# atmega_simon_says.net
KiCad netlist of a schematic drawn in EAGLE
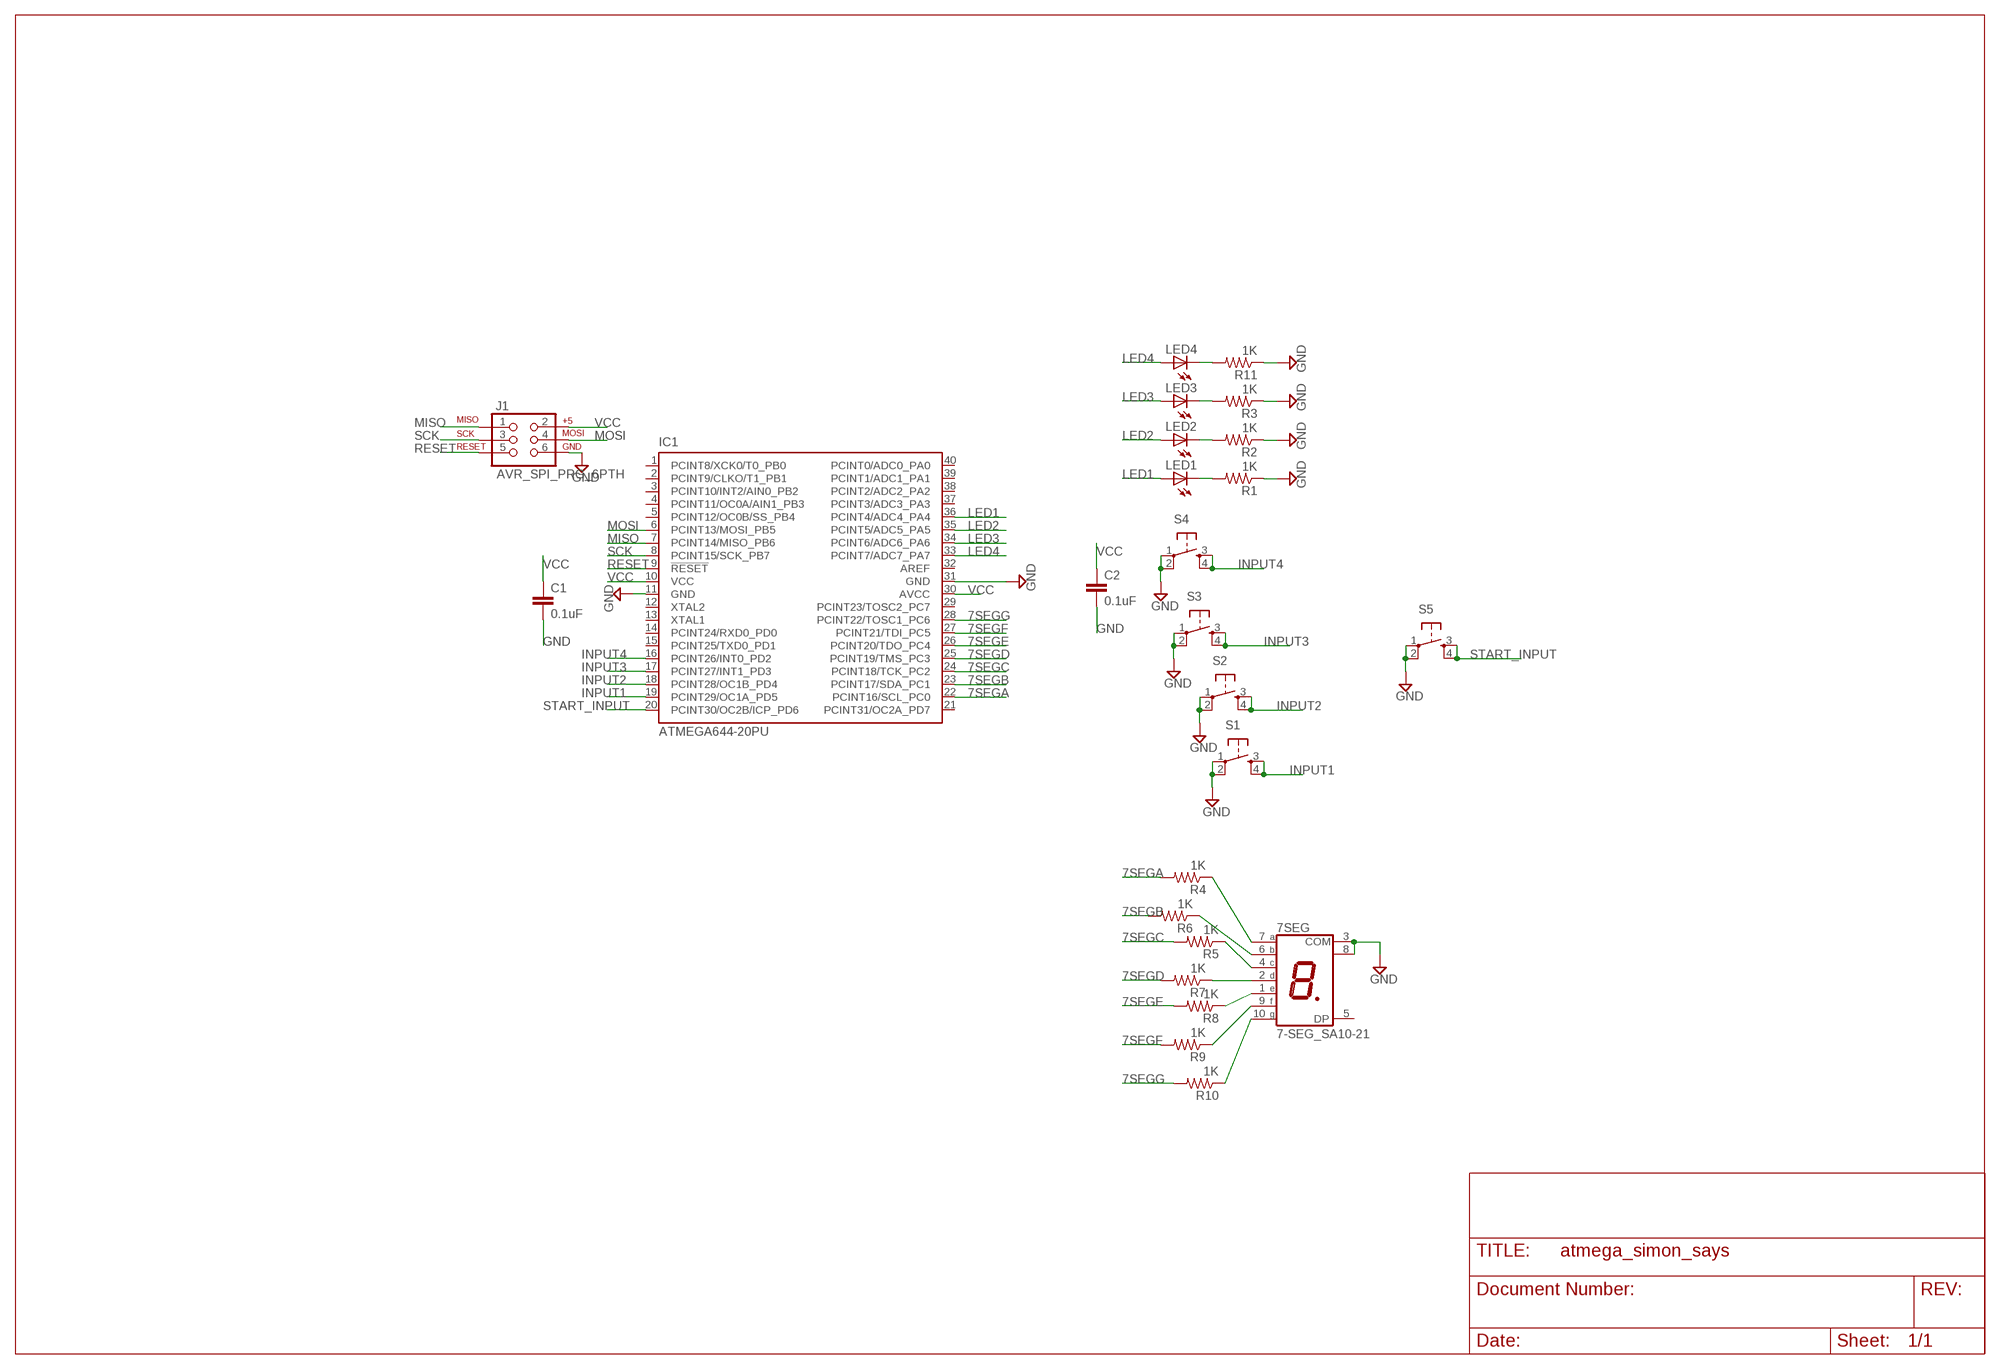
[diagram p0: schematic, sheet 1]

(export (version "E")
  (design (tool "Eeschema 10.0.6"))
  (components
    (comp (ref "7SEG")
      (value "7-SEG_SA10-21")
      (footprint "eagle-import:SA10-21")
      (libsource (lib "eagle-import") (part "7-SEG_SA10-21"))
    )
    (comp (ref "C1")
      (value "0.1uF")
      (footprint "eagle-import:0603-CAP")
      (libsource (lib "eagle-import") (part "0.1UF-25V(+80/-20%)(0603)"))
    )
    (comp (ref "C2")
      (value "0.1uF")
      (footprint "eagle-import:0603-CAP")
      (libsource (lib "eagle-import") (part "0.1UF-25V(+80/-20%)(0603)"))
    )
    (comp (ref "IC1")
      (value "ATMEGA644-20PU")
      (footprint "eagle-import:DIL40")
      (libsource (lib "eagle-import") (part "ATMEGA644-PU20"))
    )
    (comp (ref "J1")
      (value "AVR_SPI_PRG_6PTH")
      (footprint "eagle-import:2X3")
      (libsource (lib "eagle-import") (part "AVR_SPI_PRG_6PTH"))
    )
    (comp (ref "LED1")
      (value "LED3MM")
      (footprint "eagle-import:LED3MM")
      (libsource (lib "eagle-import") (part "LED3MM"))
    )
    (comp (ref "LED2")
      (value "LED3MM")
      (footprint "eagle-import:LED3MM")
      (libsource (lib "eagle-import") (part "LED3MM"))
    )
    (comp (ref "LED3")
      (value "LED3MM")
      (footprint "eagle-import:LED3MM")
      (libsource (lib "eagle-import") (part "LED3MM"))
    )
    (comp (ref "LED4")
      (value "LED3MM")
      (footprint "eagle-import:LED3MM")
      (libsource (lib "eagle-import") (part "LED3MM"))
    )
    (comp (ref "R1")
      (value "1K")
      (footprint "eagle-import:0204_5")
      (libsource (lib "eagle-import") (part "R-US_0204/5"))
    )
    (comp (ref "R2")
      (value "1K")
      (footprint "eagle-import:0204_5")
      (libsource (lib "eagle-import") (part "R-US_0204/5"))
    )
    (comp (ref "R3")
      (value "1K")
      (footprint "eagle-import:0204_5")
      (libsource (lib "eagle-import") (part "R-US_0204/5"))
    )
    (comp (ref "R4")
      (value "1K")
      (footprint "eagle-import:0204_5")
      (libsource (lib "eagle-import") (part "R-US_0204/5"))
    )
    (comp (ref "R5")
      (value "1K")
      (footprint "eagle-import:0204_5")
      (libsource (lib "eagle-import") (part "R-US_0204/5"))
    )
    (comp (ref "R6")
      (value "1K")
      (footprint "eagle-import:0204_5")
      (libsource (lib "eagle-import") (part "R-US_0204/5"))
    )
    (comp (ref "R7")
      (value "1K")
      (footprint "eagle-import:0204_5")
      (libsource (lib "eagle-import") (part "R-US_0204/5"))
    )
    (comp (ref "R8")
      (value "1K")
      (footprint "eagle-import:0204_5")
      (libsource (lib "eagle-import") (part "R-US_0204/5"))
    )
    (comp (ref "R9")
      (value "1K")
      (footprint "eagle-import:0204_5")
      (libsource (lib "eagle-import") (part "R-US_0204/5"))
    )
    (comp (ref "R10")
      (value "1K")
      (footprint "eagle-import:0204_5")
      (libsource (lib "eagle-import") (part "R-US_0204/5"))
    )
    (comp (ref "R11")
      (value "1K")
      (footprint "eagle-import:0204_5")
      (libsource (lib "eagle-import") (part "R-US_0204/5"))
    )
    (comp (ref "S1")
      (value "TAC_SWITCHPTH")
      (footprint "eagle-import:TACTILE-PTH")
      (libsource (lib "eagle-import") (part "TAC_SWITCHPTH"))
    )
    (comp (ref "S2")
      (value "TAC_SWITCHPTH")
      (footprint "eagle-import:TACTILE-PTH")
      (libsource (lib "eagle-import") (part "TAC_SWITCHPTH"))
    )
    (comp (ref "S3")
      (value "TAC_SWITCHPTH")
      (footprint "eagle-import:TACTILE-PTH")
      (libsource (lib "eagle-import") (part "TAC_SWITCHPTH"))
    )
    (comp (ref "S4")
      (value "TAC_SWITCHPTH")
      (footprint "eagle-import:TACTILE-PTH")
      (libsource (lib "eagle-import") (part "TAC_SWITCHPTH"))
    )
    (comp (ref "S5")
      (value "TAC_SWITCHPTH")
      (footprint "eagle-import:TACTILE-PTH")
      (libsource (lib "eagle-import") (part "TAC_SWITCHPTH"))
    )
  )
  (nets
    (net (code "1") (name "/7SEGA") (class "Default")
      (node (ref "IC1") (pin "22") (pinfunction "PCINT16/SCL_PC0_22") (pintype "bidirectional"))
      (node (ref "R4") (pin "2") (pinfunction "2_2") (pintype "passive"))
    )
    (net (code "2") (name "/7SEGB") (class "Default")
      (node (ref "IC1") (pin "23") (pinfunction "PCINT17/SDA_PC1_23") (pintype "bidirectional"))
      (node (ref "R6") (pin "2") (pinfunction "2_2") (pintype "passive"))
    )
    (net (code "3") (name "/7SEGC") (class "Default")
      (node (ref "IC1") (pin "24") (pinfunction "PCINT18/TCK_PC2_24") (pintype "bidirectional"))
      (node (ref "R5") (pin "2") (pinfunction "2_2") (pintype "passive"))
    )
    (net (code "4") (name "/7SEGD") (class "Default")
      (node (ref "IC1") (pin "25") (pinfunction "PCINT19/TMS_PC3_25") (pintype "bidirectional"))
      (node (ref "R7") (pin "2") (pinfunction "2_2") (pintype "passive"))
    )
    (net (code "5") (name "/7SEGE") (class "Default")
      (node (ref "IC1") (pin "26") (pinfunction "PCINT20/TDO_PC4_26") (pintype "bidirectional"))
      (node (ref "R8") (pin "2") (pinfunction "2_2") (pintype "passive"))
    )
    (net (code "6") (name "/7SEGF") (class "Default")
      (node (ref "IC1") (pin "27") (pinfunction "PCINT21/TDI_PC5_27") (pintype "bidirectional"))
      (node (ref "R9") (pin "2") (pinfunction "2_2") (pintype "passive"))
    )
    (net (code "7") (name "/7SEGG") (class "Default")
      (node (ref "IC1") (pin "28") (pinfunction "PCINT22/TOSC1_PC6_28") (pintype "bidirectional"))
      (node (ref "R10") (pin "2") (pinfunction "2_2") (pintype "passive"))
    )
    (net (code "8") (name "/INPUT1") (class "Default")
      (node (ref "IC1") (pin "19") (pinfunction "PCINT29/OC1A_PD5_19") (pintype "bidirectional"))
      (node (ref "S1") (pin "3") (pinfunction "3_3") (pintype "passive"))
      (node (ref "S1") (pin "4") (pinfunction "4_4") (pintype "passive"))
    )
    (net (code "9") (name "/INPUT2") (class "Default")
      (node (ref "IC1") (pin "18") (pinfunction "PCINT28/OC1B_PD4_18") (pintype "bidirectional"))
      (node (ref "S2") (pin "3") (pinfunction "3_3") (pintype "passive"))
      (node (ref "S2") (pin "4") (pinfunction "4_4") (pintype "passive"))
    )
    (net (code "10") (name "/INPUT3") (class "Default")
      (node (ref "IC1") (pin "17") (pinfunction "PCINT27/INT1_PD3_17") (pintype "bidirectional"))
      (node (ref "S3") (pin "3") (pinfunction "3_3") (pintype "passive"))
      (node (ref "S3") (pin "4") (pinfunction "4_4") (pintype "passive"))
    )
    (net (code "11") (name "/INPUT4") (class "Default")
      (node (ref "IC1") (pin "16") (pinfunction "PCINT26/INT0_PD2_16") (pintype "bidirectional"))
      (node (ref "S4") (pin "3") (pinfunction "3_3") (pintype "passive"))
      (node (ref "S4") (pin "4") (pinfunction "4_4") (pintype "passive"))
    )
    (net (code "12") (name "/LED1") (class "Default")
      (node (ref "IC1") (pin "36") (pinfunction "PCINT4/ADC4_PA4_36") (pintype "bidirectional"))
      (node (ref "LED1") (pin "A") (pinfunction "A_A") (pintype "passive"))
    )
    (net (code "13") (name "/LED2") (class "Default")
      (node (ref "IC1") (pin "35") (pinfunction "PCINT5/ADC5_PA5_35") (pintype "bidirectional"))
      (node (ref "LED2") (pin "A") (pinfunction "A_A") (pintype "passive"))
    )
    (net (code "14") (name "/LED3") (class "Default")
      (node (ref "IC1") (pin "34") (pinfunction "PCINT6/ADC6_PA6_34") (pintype "bidirectional"))
      (node (ref "LED3") (pin "A") (pinfunction "A_A") (pintype "passive"))
    )
    (net (code "15") (name "/LED4") (class "Default")
      (node (ref "IC1") (pin "33") (pinfunction "PCINT7/ADC7_PA7_33") (pintype "bidirectional"))
      (node (ref "LED4") (pin "A") (pinfunction "A_A") (pintype "passive"))
    )
    (net (code "16") (name "/MISO") (class "Default")
      (node (ref "IC1") (pin "7") (pinfunction "PCINT14/MISO_PB6_7") (pintype "bidirectional"))
      (node (ref "J1") (pin "1") (pinfunction "1_1") (pintype "passive"))
    )
    (net (code "17") (name "/MOSI") (class "Default")
      (node (ref "IC1") (pin "6") (pinfunction "PCINT13/MOSI_PB5_6") (pintype "bidirectional"))
      (node (ref "J1") (pin "4") (pinfunction "4_4") (pintype "passive"))
    )
    (net (code "18") (name "/RESET") (class "Default")
      (node (ref "IC1") (pin "9") (pinfunction "~{RESET}_9") (pintype "input"))
      (node (ref "J1") (pin "5") (pinfunction "5_5") (pintype "passive"))
    )
    (net (code "19") (name "/SCK") (class "Default")
      (node (ref "IC1") (pin "8") (pinfunction "PCINT15/SCK_PB7_8") (pintype "bidirectional"))
      (node (ref "J1") (pin "3") (pinfunction "3_3") (pintype "passive"))
    )
    (net (code "20") (name "/START_INPUT") (class "Default")
      (node (ref "IC1") (pin "20") (pinfunction "PCINT30/OC2B/ICP_PD6_20") (pintype "bidirectional"))
      (node (ref "S5") (pin "3") (pinfunction "3_3") (pintype "passive"))
      (node (ref "S5") (pin "4") (pinfunction "4_4") (pintype "passive"))
    )
    (net (code "21") (name "/VCC") (class "Default")
      (node (ref "C1") (pin "1") (pinfunction "1_1") (pintype "passive"))
      (node (ref "C2") (pin "1") (pinfunction "1_1") (pintype "passive"))
      (node (ref "IC1") (pin "10") (pinfunction "VCC_10") (pintype "power_in"))
      (node (ref "IC1") (pin "30") (pinfunction "AVCC_30") (pintype "power_in"))
      (node (ref "J1") (pin "2") (pinfunction "2_2") (pintype "passive"))
    )
    (net (code "22") (name "GND") (class "Default")
      (node (ref "7SEG") (pin "3") (pinfunction "COM_3") (pintype "passive"))
      (node (ref "7SEG") (pin "8") (pinfunction "COM_8") (pintype "passive"))
      (node (ref "C1") (pin "2") (pinfunction "2_2") (pintype "passive"))
      (node (ref "C2") (pin "2") (pinfunction "2_2") (pintype "passive"))
      (node (ref "IC1") (pin "11") (pinfunction "GND_11") (pintype "power_in"))
      (node (ref "IC1") (pin "31") (pinfunction "GND_31") (pintype "power_in"))
      (node (ref "J1") (pin "6") (pinfunction "6_6") (pintype "passive"))
      (node (ref "R1") (pin "1") (pinfunction "1_1") (pintype "passive"))
      (node (ref "R11") (pin "1") (pinfunction "1_1") (pintype "passive"))
      (node (ref "R2") (pin "1") (pinfunction "1_1") (pintype "passive"))
      (node (ref "R3") (pin "1") (pinfunction "1_1") (pintype "passive"))
      (node (ref "S1") (pin "1") (pinfunction "1_1") (pintype "passive"))
      (node (ref "S1") (pin "2") (pinfunction "2_2") (pintype "passive"))
      (node (ref "S2") (pin "1") (pinfunction "1_1") (pintype "passive"))
      (node (ref "S2") (pin "2") (pinfunction "2_2") (pintype "passive"))
      (node (ref "S3") (pin "1") (pinfunction "1_1") (pintype "passive"))
      (node (ref "S3") (pin "2") (pinfunction "2_2") (pintype "passive"))
      (node (ref "S4") (pin "1") (pinfunction "1_1") (pintype "passive"))
      (node (ref "S4") (pin "2") (pinfunction "2_2") (pintype "passive"))
      (node (ref "S5") (pin "1") (pinfunction "1_1") (pintype "passive"))
      (node (ref "S5") (pin "2") (pinfunction "2_2") (pintype "passive"))
    )
    (net (code "23") (name "Net-(7SEG-A)") (class "Default")
      (node (ref "7SEG") (pin "7") (pinfunction "A_7") (pintype "passive"))
      (node (ref "R4") (pin "1") (pinfunction "1_1") (pintype "passive"))
    )
    (net (code "24") (name "Net-(7SEG-B)") (class "Default")
      (node (ref "7SEG") (pin "6") (pinfunction "B_6") (pintype "passive"))
      (node (ref "R6") (pin "1") (pinfunction "1_1") (pintype "passive"))
    )
    (net (code "25") (name "Net-(7SEG-C)") (class "Default")
      (node (ref "7SEG") (pin "4") (pinfunction "C_4") (pintype "passive"))
      (node (ref "R5") (pin "1") (pinfunction "1_1") (pintype "passive"))
    )
    (net (code "26") (name "Net-(7SEG-D)") (class "Default")
      (node (ref "7SEG") (pin "2") (pinfunction "D_2") (pintype "passive"))
      (node (ref "R7") (pin "1") (pinfunction "1_1") (pintype "passive"))
    )
    (net (code "27") (name "Net-(7SEG-E)") (class "Default")
      (node (ref "7SEG") (pin "1") (pinfunction "E_1") (pintype "passive"))
      (node (ref "R8") (pin "1") (pinfunction "1_1") (pintype "passive"))
    )
    (net (code "28") (name "Net-(7SEG-F)") (class "Default")
      (node (ref "7SEG") (pin "9") (pinfunction "F_9") (pintype "passive"))
      (node (ref "R9") (pin "1") (pinfunction "1_1") (pintype "passive"))
    )
    (net (code "29") (name "Net-(7SEG-G)") (class "Default")
      (node (ref "7SEG") (pin "10") (pinfunction "G_10") (pintype "passive"))
      (node (ref "R10") (pin "1") (pinfunction "1_1") (pintype "passive"))
    )
    (net (code "30") (name "Net-(LED1-C)") (class "Default")
      (node (ref "LED1") (pin "K") (pinfunction "C_K") (pintype "passive"))
      (node (ref "R1") (pin "2") (pinfunction "2_2") (pintype "passive"))
    )
    (net (code "31") (name "Net-(LED2-C)") (class "Default")
      (node (ref "LED2") (pin "K") (pinfunction "C_K") (pintype "passive"))
      (node (ref "R2") (pin "2") (pinfunction "2_2") (pintype "passive"))
    )
    (net (code "32") (name "Net-(LED3-C)") (class "Default")
      (node (ref "LED3") (pin "K") (pinfunction "C_K") (pintype "passive"))
      (node (ref "R3") (pin "2") (pinfunction "2_2") (pintype "passive"))
    )
    (net (code "33") (name "Net-(LED4-C)") (class "Default")
      (node (ref "LED4") (pin "K") (pinfunction "C_K") (pintype "passive"))
      (node (ref "R11") (pin "2") (pinfunction "2_2") (pintype "passive"))
    )
    (net (code "34") (name "unconnected-(7SEG-DP-Pad5)") (class "Default")
      (node (ref "7SEG") (pin "5") (pinfunction "DP_5") (pintype "passive"))
    )
    (net (code "35") (name "unconnected-(IC1-AREF-Pad32)") (class "Default")
      (node (ref "IC1") (pin "32") (pinfunction "AREF_32") (pintype "passive"))
    )
    (net (code "36") (name "unconnected-(IC1-PCINT0{slash}ADC0_PA0-Pad40)") (class "Default")
      (node (ref "IC1") (pin "40") (pinfunction "PCINT0/ADC0_PA0_40") (pintype "bidirectional"))
    )
    (net (code "37") (name "unconnected-(IC1-PCINT1{slash}ADC1_PA1-Pad39)") (class "Default")
      (node (ref "IC1") (pin "39") (pinfunction "PCINT1/ADC1_PA1_39") (pintype "bidirectional"))
    )
    (net (code "38") (name "unconnected-(IC1-PCINT2{slash}ADC2_PA2-Pad38)") (class "Default")
      (node (ref "IC1") (pin "38") (pinfunction "PCINT2/ADC2_PA2_38") (pintype "bidirectional"))
    )
    (net (code "39") (name "unconnected-(IC1-PCINT3{slash}ADC3_PA3-Pad37)") (class "Default")
      (node (ref "IC1") (pin "37") (pinfunction "PCINT3/ADC3_PA3_37") (pintype "bidirectional"))
    )
    (net (code "40") (name "unconnected-(IC1-PCINT8{slash}XCK0{slash}T0_PB0-Pad1)") (class "Default")
      (node (ref "IC1") (pin "1") (pinfunction "PCINT8/XCK0/T0_PB0_1") (pintype "bidirectional"))
    )
    (net (code "41") (name "unconnected-(IC1-PCINT9{slash}CLKO{slash}T1_PB1-Pad2)") (class "Default")
      (node (ref "IC1") (pin "2") (pinfunction "PCINT9/CLKO/T1_PB1_2") (pintype "bidirectional"))
    )
    (net (code "42") (name "unconnected-(IC1-PCINT10{slash}INT2{slash}AIN0_PB2-Pad3)") (class "Default")
      (node (ref "IC1") (pin "3") (pinfunction "PCINT10/INT2/AIN0_PB2_3") (pintype "bidirectional"))
    )
    (net (code "43") (name "unconnected-(IC1-PCINT11{slash}OC0A{slash}AIN1_PB3-Pad4)") (class "Default")
      (node (ref "IC1") (pin "4") (pinfunction "PCINT11/OC0A/AIN1_PB3_4") (pintype "bidirectional"))
    )
    (net (code "44") (name "unconnected-(IC1-PCINT12{slash}OC0B{slash}SS_PB4-Pad5)") (class "Default")
      (node (ref "IC1") (pin "5") (pinfunction "PCINT12/OC0B/SS_PB4_5") (pintype "bidirectional"))
    )
    (net (code "45") (name "unconnected-(IC1-PCINT23{slash}TOSC2_PC7-Pad29)") (class "Default")
      (node (ref "IC1") (pin "29") (pinfunction "PCINT23/TOSC2_PC7_29") (pintype "bidirectional"))
    )
    (net (code "46") (name "unconnected-(IC1-PCINT24{slash}RXD0_PD0-Pad14)") (class "Default")
      (node (ref "IC1") (pin "14") (pinfunction "PCINT24/RXD0_PD0_14") (pintype "bidirectional"))
    )
    (net (code "47") (name "unconnected-(IC1-PCINT25{slash}TXD0_PD1-Pad15)") (class "Default")
      (node (ref "IC1") (pin "15") (pinfunction "PCINT25/TXD0_PD1_15") (pintype "bidirectional"))
    )
    (net (code "48") (name "unconnected-(IC1-PCINT31{slash}OC2A_PD7-Pad21)") (class "Default")
      (node (ref "IC1") (pin "21") (pinfunction "PCINT31/OC2A_PD7_21") (pintype "bidirectional"))
    )
    (net (code "49") (name "unconnected-(IC1-XTAL1-Pad13)") (class "Default")
      (node (ref "IC1") (pin "13") (pinfunction "XTAL1_13") (pintype "input"))
    )
    (net (code "50") (name "unconnected-(IC1-XTAL2-Pad12)") (class "Default")
      (node (ref "IC1") (pin "12") (pinfunction "XTAL2_12") (pintype "output"))
    )
  )
)
